# Hanover_Flipdot_Featherwing.net
KiCad netlist of a schematic drawn in EAGLE
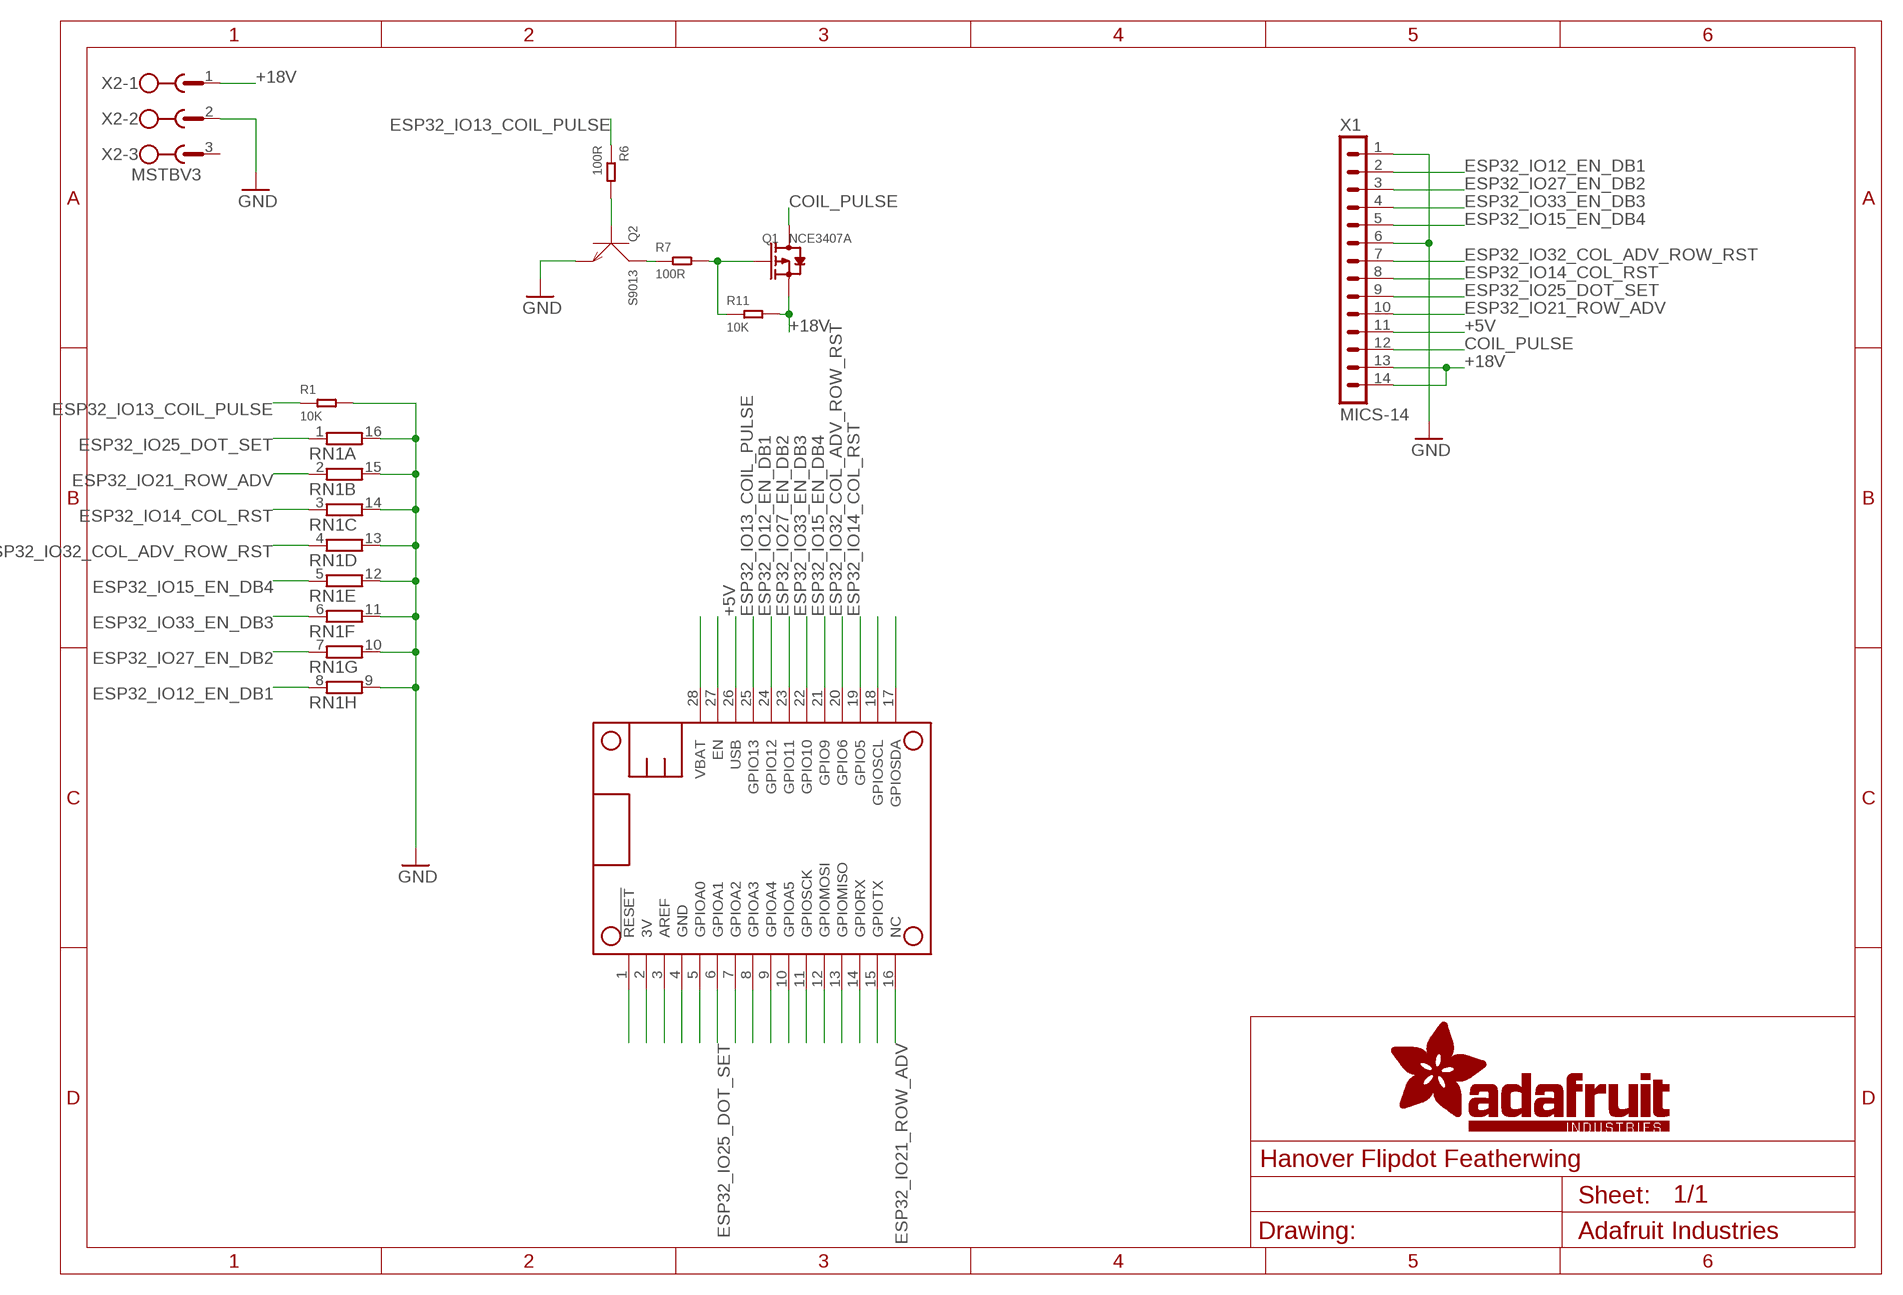
[diagram p0: schematic, sheet 1]

(export (version "E")
  (design (tool "Eeschema 10.0.6"))
  (components
    (comp (ref "MS1")
      (value "FEATHERWING")
      (footprint "eagle-import:FEATHERWING")
      (libsource (lib "eagle-import") (part "FEATHERWING"))
    )
    (comp (ref "Q1")
      (value "NCE3407A")
      (footprint "eagle-import:SOT-23")
      (libsource (lib "eagle-import") (part "SMD-MOSFET-P-CH-VDC=30V-ID=4.3A-NCE3407A(SOT-23)"))
    )
    (comp (ref "Q2")
      (value "S9013")
      (footprint "eagle-import:SOT-23")
      (libsource (lib "eagle-import") (part "SMD-TRANSISTORS-NPN-25V-500MA-S9013(SOT-23)"))
    )
    (comp (ref "R1")
      (value "10K")
      (footprint "eagle-import:R0603")
      (fields (field (name "MPN") "RC0603FR-0710KL"))
      (libsource (lib "eagle-import") (part "SMD-RES-10K-1%-1/10W(0603)"))
    )
    (comp (ref "R6")
      (value "100R")
      (footprint "eagle-import:R0603")
      (fields (field (name "MPN") "RC0603JR-07100RL"))
      (libsource (lib "eagle-import") (part "SMD-RES-100R-5%-1/10W(0603)"))
    )
    (comp (ref "R7")
      (value "100R")
      (footprint "eagle-import:R0603")
      (fields (field (name "MPN") "RC0603JR-07100RL"))
      (libsource (lib "eagle-import") (part "SMD-RES-100R-5%-1/10W(0603)"))
    )
    (comp (ref "R11")
      (value "10K")
      (footprint "eagle-import:R0603")
      (fields (field (name "MPN") "RC0603FR-0710KL"))
      (libsource (lib "eagle-import") (part "SMD-RES-10K-1%-1/10W(0603)"))
    )
    (comp (ref "RN1")
      (value "8R-NEXB2HV")
      (footprint "eagle-import:EXB2HV")
      (libsource (lib "eagle-import") (part "8R-NEXB2HV"))
    )
    (comp (ref "X1")
      (value "MICS-14")
      (footprint "eagle-import:MICS-14")
      (libsource (lib "eagle-import") (part "MICS-14"))
    )
    (comp (ref "X2")
      (value "MSTBV3")
      (footprint "eagle-import:MSTBV3")
      (fields (field (name "MPN") "MSTBV 2,5/3-GF-5.08"))
      (libsource (lib "eagle-import") (part "MSTBV3"))
    )
  )
  (nets
    (net (code "1") (name "/+5V") (class "Default")
      (node (ref "MS1") (pin "26") (pinfunction "USB_26") (pintype "power_in"))
      (node (ref "X1") (pin "11") (pinfunction "11_11") (pintype "passive"))
    )
    (net (code "2") (name "/+18V") (class "Default")
      (node (ref "Q1") (pin "2") (pinfunction "S_2") (pintype "passive"))
      (node (ref "R11") (pin "2") (pinfunction "2_2") (pintype "passive"))
      (node (ref "X1") (pin "13") (pinfunction "13_13") (pintype "passive"))
      (node (ref "X1") (pin "14") (pinfunction "14_14") (pintype "passive"))
      (node (ref "X2") (pin "1") (pinfunction "1_1") (pintype "passive"))
    )
    (net (code "3") (name "/COIL_PULSE") (class "Default")
      (node (ref "Q1") (pin "3") (pinfunction "D_3") (pintype "passive"))
      (node (ref "X1") (pin "12") (pinfunction "12_12") (pintype "passive"))
    )
    (net (code "4") (name "/ESP32_IO12_EN_DB1") (class "Default")
      (node (ref "MS1") (pin "24") (pinfunction "GPIO12_24") (pintype "bidirectional"))
      (node (ref "RN1") (pin "8") (pinfunction "1_8") (pintype "passive"))
      (node (ref "X1") (pin "2") (pinfunction "2_2") (pintype "passive"))
    )
    (net (code "5") (name "/ESP32_IO13_COIL_PULSE") (class "Default")
      (node (ref "MS1") (pin "25") (pinfunction "GPIO13_25") (pintype "bidirectional"))
      (node (ref "R1") (pin "1") (pinfunction "1_1") (pintype "passive"))
      (node (ref "R6") (pin "1") (pinfunction "1_1") (pintype "passive"))
    )
    (net (code "6") (name "/ESP32_IO14_COL_RST") (class "Default")
      (node (ref "MS1") (pin "19") (pinfunction "GPIO5_19") (pintype "bidirectional"))
      (node (ref "RN1") (pin "3") (pinfunction "1_3") (pintype "passive"))
      (node (ref "X1") (pin "8") (pinfunction "8_8") (pintype "passive"))
    )
    (net (code "7") (name "/ESP32_IO15_EN_DB4") (class "Default")
      (node (ref "MS1") (pin "21") (pinfunction "GPIO9_21") (pintype "bidirectional"))
      (node (ref "RN1") (pin "5") (pinfunction "1_5") (pintype "passive"))
      (node (ref "X1") (pin "5") (pinfunction "5_5") (pintype "passive"))
    )
    (net (code "8") (name "/ESP32_IO21_ROW_ADV") (class "Default")
      (node (ref "MS1") (pin "16") (pinfunction "NC_16") (pintype "passive"))
      (node (ref "RN1") (pin "2") (pinfunction "1_2") (pintype "passive"))
      (node (ref "X1") (pin "10") (pinfunction "10_10") (pintype "passive"))
    )
    (net (code "9") (name "/ESP32_IO25_DOT_SET") (class "Default")
      (node (ref "MS1") (pin "6") (pinfunction "GPIOA1_6") (pintype "bidirectional"))
      (node (ref "RN1") (pin "1") (pinfunction "1_1") (pintype "passive"))
      (node (ref "X1") (pin "9") (pinfunction "9_9") (pintype "passive"))
    )
    (net (code "10") (name "/ESP32_IO27_EN_DB2") (class "Default")
      (node (ref "MS1") (pin "23") (pinfunction "GPIO11_23") (pintype "bidirectional"))
      (node (ref "RN1") (pin "7") (pinfunction "1_7") (pintype "passive"))
      (node (ref "X1") (pin "3") (pinfunction "3_3") (pintype "passive"))
    )
    (net (code "11") (name "/ESP32_IO32_COL_ADV_ROW_RST") (class "Default")
      (node (ref "MS1") (pin "20") (pinfunction "GPIO6_20") (pintype "bidirectional"))
      (node (ref "RN1") (pin "4") (pinfunction "1_4") (pintype "passive"))
      (node (ref "X1") (pin "7") (pinfunction "7_7") (pintype "passive"))
    )
    (net (code "12") (name "/ESP32_IO33_EN_DB3") (class "Default")
      (node (ref "MS1") (pin "22") (pinfunction "GPIO10_22") (pintype "bidirectional"))
      (node (ref "RN1") (pin "6") (pinfunction "1_6") (pintype "passive"))
      (node (ref "X1") (pin "4") (pinfunction "4_4") (pintype "passive"))
    )
    (net (code "13") (name "GND") (class "Default")
      (node (ref "MS1") (pin "4") (pinfunction "GND_4") (pintype "power_in"))
      (node (ref "Q2") (pin "2") (pinfunction "E_2") (pintype "passive"))
      (node (ref "R1") (pin "2") (pinfunction "2_2") (pintype "passive"))
      (node (ref "RN1") (pin "10") (pinfunction "2_10") (pintype "passive"))
      (node (ref "RN1") (pin "11") (pinfunction "2_11") (pintype "passive"))
      (node (ref "RN1") (pin "12") (pinfunction "2_12") (pintype "passive"))
      (node (ref "RN1") (pin "13") (pinfunction "2_13") (pintype "passive"))
      (node (ref "RN1") (pin "14") (pinfunction "2_14") (pintype "passive"))
      (node (ref "RN1") (pin "15") (pinfunction "2_15") (pintype "passive"))
      (node (ref "RN1") (pin "16") (pinfunction "2_16") (pintype "passive"))
      (node (ref "RN1") (pin "9") (pinfunction "2_9") (pintype "passive"))
      (node (ref "X1") (pin "1") (pinfunction "1_1") (pintype "passive"))
      (node (ref "X1") (pin "6") (pinfunction "6_6") (pintype "passive"))
      (node (ref "X2") (pin "2") (pinfunction "1_2") (pintype "passive"))
    )
    (net (code "14") (name "Net-(Q1-G)") (class "Default")
      (node (ref "Q1") (pin "1") (pinfunction "G_1") (pintype "passive"))
      (node (ref "R11") (pin "1") (pinfunction "1_1") (pintype "passive"))
      (node (ref "R7") (pin "2") (pinfunction "2_2") (pintype "passive"))
    )
    (net (code "15") (name "Net-(Q2-B)") (class "Default")
      (node (ref "Q2") (pin "1") (pinfunction "B_1") (pintype "passive"))
      (node (ref "R6") (pin "2") (pinfunction "2_2") (pintype "passive"))
    )
    (net (code "16") (name "Net-(Q2-C)") (class "Default")
      (node (ref "Q2") (pin "3") (pinfunction "C_3") (pintype "passive"))
      (node (ref "R7") (pin "1") (pinfunction "1_1") (pintype "passive"))
    )
    (net (code "17") (name "unconnected-(MS1-3V-Pad2)") (class "Default")
      (node (ref "MS1") (pin "2") (pinfunction "3V_2") (pintype "power_in"))
    )
    (net (code "18") (name "unconnected-(MS1-AREF-Pad3)") (class "Default")
      (node (ref "MS1") (pin "3") (pinfunction "AREF_3") (pintype "passive"))
    )
    (net (code "19") (name "unconnected-(MS1-EN-Pad27)") (class "Default")
      (node (ref "MS1") (pin "27") (pinfunction "EN_27") (pintype "passive"))
    )
    (net (code "20") (name "unconnected-(MS1-GPIOA0-Pad5)") (class "Default")
      (node (ref "MS1") (pin "5") (pinfunction "GPIOA0_5") (pintype "bidirectional"))
    )
    (net (code "21") (name "unconnected-(MS1-GPIOA2-Pad7)") (class "Default")
      (node (ref "MS1") (pin "7") (pinfunction "GPIOA2_7") (pintype "bidirectional"))
    )
    (net (code "22") (name "unconnected-(MS1-GPIOA3-Pad8)") (class "Default")
      (node (ref "MS1") (pin "8") (pinfunction "GPIOA3_8") (pintype "bidirectional"))
    )
    (net (code "23") (name "unconnected-(MS1-GPIOA4-Pad9)") (class "Default")
      (node (ref "MS1") (pin "9") (pinfunction "GPIOA4_9") (pintype "bidirectional"))
    )
    (net (code "24") (name "unconnected-(MS1-GPIOA5-Pad10)") (class "Default")
      (node (ref "MS1") (pin "10") (pinfunction "GPIOA5_10") (pintype "bidirectional"))
    )
    (net (code "25") (name "unconnected-(MS1-GPIOMISO-Pad13)") (class "Default")
      (node (ref "MS1") (pin "13") (pinfunction "GPIOMISO_13") (pintype "bidirectional"))
    )
    (net (code "26") (name "unconnected-(MS1-GPIOMOSI-Pad12)") (class "Default")
      (node (ref "MS1") (pin "12") (pinfunction "GPIOMOSI_12") (pintype "bidirectional"))
    )
    (net (code "27") (name "unconnected-(MS1-GPIORX-Pad14)") (class "Default")
      (node (ref "MS1") (pin "14") (pinfunction "GPIORX_14") (pintype "bidirectional"))
    )
    (net (code "28") (name "unconnected-(MS1-GPIOSCK-Pad11)") (class "Default")
      (node (ref "MS1") (pin "11") (pinfunction "GPIOSCK_11") (pintype "bidirectional"))
    )
    (net (code "29") (name "unconnected-(MS1-GPIOSCL-Pad18)") (class "Default")
      (node (ref "MS1") (pin "18") (pinfunction "GPIOSCL_18") (pintype "bidirectional"))
    )
    (net (code "30") (name "unconnected-(MS1-GPIOSDA-Pad17)") (class "Default")
      (node (ref "MS1") (pin "17") (pinfunction "GPIOSDA_17") (pintype "bidirectional"))
    )
    (net (code "31") (name "unconnected-(MS1-GPIOTX-Pad15)") (class "Default")
      (node (ref "MS1") (pin "15") (pinfunction "GPIOTX_15") (pintype "bidirectional"))
    )
    (net (code "32") (name "unconnected-(MS1-VBAT-Pad28)") (class "Default")
      (node (ref "MS1") (pin "28") (pinfunction "VBAT_28") (pintype "power_in"))
    )
    (net (code "33") (name "unconnected-(MS1-~{RESET}-Pad1)") (class "Default")
      (node (ref "MS1") (pin "1") (pinfunction "~{RESET}_1") (pintype "input"))
    )
    (net (code "34") (name "unconnected-(X2C-1-Pad3)") (class "Default")
      (node (ref "X2") (pin "3") (pinfunction "1_3") (pintype "passive"))
    )
  )
)
